# 3_INTERFACE_PWR_LS_HS.net
KiCad netlist of a schematic drawn in Altium Designer
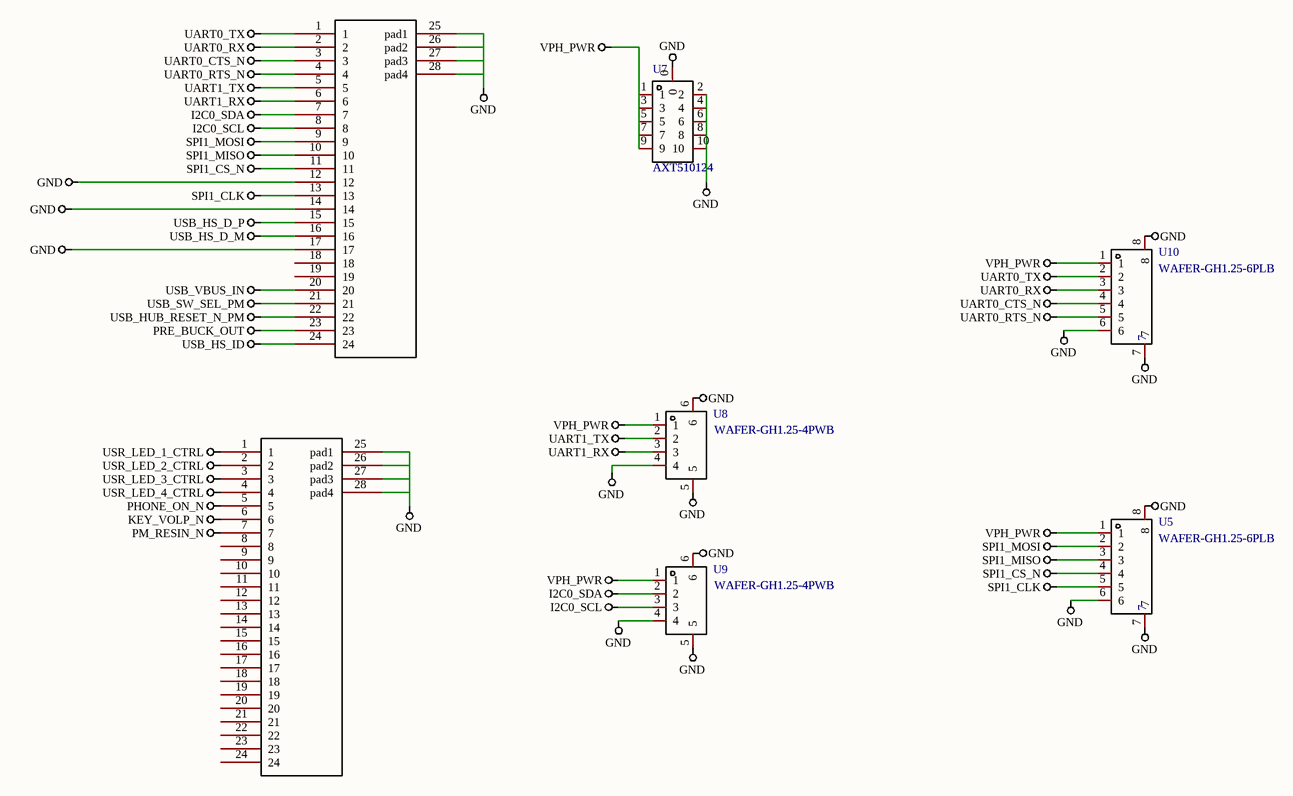
[diagram p0: 3_INTERFACE_PWR_LS_HS.schdoc]

(export (version "E")
  (design (tool "Eeschema 10.0.6"))
  (components
    (comp (ref "CN1")
      (value "CON24_0")
      (fields (field (name "LIBRARY NAME") "MSM8916_DRAM_PMIC_REF_Library"))
      (libsource (lib "altium-import") (part "root_0_CON24_0_"))
    )
    (comp (ref "CN2")
      (value "CON24_0")
      (fields (field (name "LIBRARY NAME") "MSM8916_DRAM_PMIC_REF_Library"))
      (libsource (lib "altium-import") (part "root_0_CON24_0_"))
    )
    (comp (ref "U5")
      (value "WAFER-GH1.25-6PLB")
      (description "参考系列:GH;间距:1.25mm;插针结构:1x6P;排数:1;每排PIN数:6;公母:公型插针;安装方式:立贴;额定电流:1A;工作温度范围:-25℃~+85℃;")
      (fields
        (field (name "NAME") "WAFER-GH1.25-6PLB")
        (field (name "MANUFACTURER") "XUNPU(讯普)")
        (field (name "NAME_1") "7")
      )
      (libsource (lib "altium-import") (part "root_0_WAFER-GH1.25-6PLB_"))
    )
    (comp (ref "U7")
      (value "AXT510124")
      (description "PIN总数:10;间距:0.4mm;行数:2;公母:母;安装方式:立贴;")
      (fields (field (name "NAME") "AXT510124") (field (name "MANUFACTURER") "PANASONIC(松下)"))
      (libsource (lib "altium-import") (part "root_0_AXT510124_"))
    )
    (comp (ref "U8")
      (value "WAFER-GH1.25-4PWB")
      (description "参考系列:GH;间距:1.25mm;插针结构:1x4P;排数:1;每排PIN数:4;公母:公型插针;安装方式:卧贴;额定电流:1A;工作温度范围:-25℃~+85℃;")
      (fields (field (name "NAME") "WAFER-GH1.25-4PWB") (field (name "MANUFACTURER") "XUNPU(讯普)"))
      (libsource (lib "altium-import") (part "root_0_WAFER-GH1.25-4PWB_"))
    )
    (comp (ref "U9")
      (value "WAFER-GH1.25-4PWB")
      (description "参考系列:GH;间距:1.25mm;插针结构:1x4P;排数:1;每排PIN数:4;公母:公型插针;安装方式:卧贴;额定电流:1A;工作温度范围:-25℃~+85℃;")
      (fields (field (name "NAME") "WAFER-GH1.25-4PWB") (field (name "MANUFACTURER") "XUNPU(讯普)"))
      (libsource (lib "altium-import") (part "root_0_WAFER-GH1.25-4PWB_"))
    )
    (comp (ref "U10")
      (value "WAFER-GH1.25-6PLB")
      (description "参考系列:GH;间距:1.25mm;插针结构:1x6P;排数:1;每排PIN数:6;公母:公型插针;安装方式:立贴;额定电流:1A;工作温度范围:-25℃~+85℃;")
      (fields
        (field (name "NAME") "WAFER-GH1.25-6PLB")
        (field (name "MANUFACTURER") "XUNPU(讯普)")
        (field (name "NAME_1") "7")
      )
      (libsource (lib "altium-import") (part "root_0_WAFER-GH1.25-6PLB_"))
    )
  )
  (nets
    (net (code "1") (name "GND") (class "Default")
      (node (ref "CN1") (pin "12") (pinfunction "12_12") (pintype "passive"))
      (node (ref "CN1") (pin "14") (pinfunction "14_14") (pintype "passive"))
      (node (ref "CN1") (pin "17") (pinfunction "17_17") (pintype "passive"))
      (node (ref "CN1") (pin "25") (pinfunction "pad1_25") (pintype "passive"))
      (node (ref "CN1") (pin "26") (pinfunction "pad2_26") (pintype "passive"))
      (node (ref "CN1") (pin "27") (pinfunction "pad3_27") (pintype "passive"))
      (node (ref "CN1") (pin "28") (pinfunction "pad4_28") (pintype "passive"))
      (node (ref "CN2") (pin "25") (pinfunction "pad1_25") (pintype "passive"))
      (node (ref "CN2") (pin "26") (pinfunction "pad2_26") (pintype "passive"))
      (node (ref "CN2") (pin "27") (pinfunction "pad3_27") (pintype "passive"))
      (node (ref "CN2") (pin "28") (pinfunction "pad4_28") (pintype "passive"))
      (node (ref "U10") (pin "6") (pinfunction "6_6") (pintype "passive"))
      (node (ref "U10") (pin "7") (pinfunction "7_7") (pintype "passive"))
      (node (ref "U10") (pin "8") (pinfunction "8_8") (pintype "passive"))
      (node (ref "U5") (pin "6") (pinfunction "6_6") (pintype "passive"))
      (node (ref "U5") (pin "7") (pinfunction "7_7") (pintype "passive"))
      (node (ref "U5") (pin "8") (pinfunction "8_8") (pintype "passive"))
      (node (ref "U7") (pin "0") (pinfunction "0_0") (pintype "passive"))
      (node (ref "U7") (pin "10") (pinfunction "10_10") (pintype "passive"))
      (node (ref "U7") (pin "2") (pinfunction "2_2") (pintype "passive"))
      (node (ref "U7") (pin "4") (pinfunction "4_4") (pintype "passive"))
      (node (ref "U7") (pin "6") (pinfunction "6_6") (pintype "passive"))
      (node (ref "U7") (pin "8") (pinfunction "8_8") (pintype "passive"))
      (node (ref "U8") (pin "4") (pinfunction "4_4") (pintype "passive"))
      (node (ref "U8") (pin "5") (pinfunction "5_5") (pintype "passive"))
      (node (ref "U8") (pin "6") (pinfunction "6_6") (pintype "passive"))
      (node (ref "U9") (pin "4") (pinfunction "4_4") (pintype "passive"))
      (node (ref "U9") (pin "5") (pinfunction "5_5") (pintype "passive"))
      (node (ref "U9") (pin "6") (pinfunction "6_6") (pintype "passive"))
    )
    (net (code "2") (name "I2C0_SCL") (class "Default")
      (node (ref "CN1") (pin "8") (pinfunction "8_8") (pintype "passive"))
      (node (ref "U9") (pin "3") (pinfunction "3_3") (pintype "passive"))
    )
    (net (code "3") (name "I2C0_SDA") (class "Default")
      (node (ref "CN1") (pin "7") (pinfunction "7_7") (pintype "passive"))
      (node (ref "U9") (pin "2") (pinfunction "2_2") (pintype "passive"))
    )
    (net (code "4") (name "KEY_VOLP_N") (class "Default")
      (node (ref "CN2") (pin "6") (pinfunction "6_6") (pintype "passive"))
    )
    (net (code "5") (name "PHONE_ON_N") (class "Default")
      (node (ref "CN2") (pin "5") (pinfunction "5_5") (pintype "passive"))
    )
    (net (code "6") (name "PM_RESIN_N") (class "Default")
      (node (ref "CN2") (pin "7") (pinfunction "7_7") (pintype "passive"))
    )
    (net (code "7") (name "PRE_BUCK_OUT") (class "Default")
      (node (ref "CN1") (pin "23") (pinfunction "23_23") (pintype "passive"))
    )
    (net (code "8") (name "SPI1_CLK") (class "Default")
      (node (ref "CN1") (pin "13") (pinfunction "13_13") (pintype "passive"))
      (node (ref "U5") (pin "5") (pinfunction "5_5") (pintype "passive"))
    )
    (net (code "9") (name "SPI1_CS_N") (class "Default")
      (node (ref "CN1") (pin "11") (pinfunction "11_11") (pintype "passive"))
      (node (ref "U5") (pin "4") (pinfunction "4_4") (pintype "passive"))
    )
    (net (code "10") (name "SPI1_MISO") (class "Default")
      (node (ref "CN1") (pin "10") (pinfunction "10_10") (pintype "passive"))
      (node (ref "U5") (pin "3") (pinfunction "3_3") (pintype "passive"))
    )
    (net (code "11") (name "SPI1_MOSI") (class "Default")
      (node (ref "CN1") (pin "9") (pinfunction "9_9") (pintype "passive"))
      (node (ref "U5") (pin "2") (pinfunction "2_2") (pintype "passive"))
    )
    (net (code "12") (name "UART0_CTS_N") (class "Default")
      (node (ref "CN1") (pin "3") (pinfunction "3_3") (pintype "passive"))
      (node (ref "U10") (pin "4") (pinfunction "4_4") (pintype "passive"))
    )
    (net (code "13") (name "UART0_RTS_N") (class "Default")
      (node (ref "CN1") (pin "4") (pinfunction "4_4") (pintype "passive"))
      (node (ref "U10") (pin "5") (pinfunction "5_5") (pintype "passive"))
    )
    (net (code "14") (name "UART0_RX") (class "Default")
      (node (ref "CN1") (pin "2") (pinfunction "2_2") (pintype "passive"))
      (node (ref "U10") (pin "3") (pinfunction "3_3") (pintype "passive"))
    )
    (net (code "15") (name "UART0_TX") (class "Default")
      (node (ref "CN1") (pin "1") (pinfunction "1_1") (pintype "passive"))
      (node (ref "U10") (pin "2") (pinfunction "2_2") (pintype "passive"))
    )
    (net (code "16") (name "UART1_RX") (class "Default")
      (node (ref "CN1") (pin "6") (pinfunction "6_6") (pintype "passive"))
      (node (ref "U8") (pin "3") (pinfunction "3_3") (pintype "passive"))
    )
    (net (code "17") (name "UART1_TX") (class "Default")
      (node (ref "CN1") (pin "5") (pinfunction "5_5") (pintype "passive"))
      (node (ref "U8") (pin "2") (pinfunction "2_2") (pintype "passive"))
    )
    (net (code "18") (name "USB_HS_D_M") (class "Default")
      (node (ref "CN1") (pin "16") (pinfunction "16_16") (pintype "passive"))
    )
    (net (code "19") (name "USB_HS_D_P") (class "Default")
      (node (ref "CN1") (pin "15") (pinfunction "15_15") (pintype "passive"))
    )
    (net (code "20") (name "USB_HS_ID") (class "Default")
      (node (ref "CN1") (pin "24") (pinfunction "24_24") (pintype "passive"))
    )
    (net (code "21") (name "USB_HUB_RESET_N_PM") (class "Default")
      (node (ref "CN1") (pin "22") (pinfunction "22_22") (pintype "passive"))
    )
    (net (code "22") (name "USB_SW_SEL_PM") (class "Default")
      (node (ref "CN1") (pin "21") (pinfunction "21_21") (pintype "passive"))
    )
    (net (code "23") (name "USB_VBUS_IN") (class "Default")
      (node (ref "CN1") (pin "20") (pinfunction "20_20") (pintype "passive"))
    )
    (net (code "24") (name "USR_LED_1_CTRL") (class "Default")
      (node (ref "CN2") (pin "1") (pinfunction "1_1") (pintype "passive"))
    )
    (net (code "25") (name "USR_LED_2_CTRL") (class "Default")
      (node (ref "CN2") (pin "2") (pinfunction "2_2") (pintype "passive"))
    )
    (net (code "26") (name "USR_LED_3_CTRL") (class "Default")
      (node (ref "CN2") (pin "3") (pinfunction "3_3") (pintype "passive"))
    )
    (net (code "27") (name "USR_LED_4_CTRL") (class "Default")
      (node (ref "CN2") (pin "4") (pinfunction "4_4") (pintype "passive"))
    )
    (net (code "28") (name "VPH_PWR") (class "Default")
      (node (ref "U10") (pin "1") (pinfunction "1_1") (pintype "passive"))
      (node (ref "U5") (pin "1") (pinfunction "1_1") (pintype "passive"))
      (node (ref "U7") (pin "1") (pinfunction "1_1") (pintype "passive"))
      (node (ref "U7") (pin "3") (pinfunction "3_3") (pintype "passive"))
      (node (ref "U7") (pin "5") (pinfunction "5_5") (pintype "passive"))
      (node (ref "U7") (pin "7") (pinfunction "7_7") (pintype "passive"))
      (node (ref "U7") (pin "9") (pinfunction "9_9") (pintype "passive"))
      (node (ref "U8") (pin "1") (pinfunction "1_1") (pintype "passive"))
      (node (ref "U9") (pin "1") (pinfunction "1_1") (pintype "passive"))
    )
    (net (code "29") (name "unconnected-(CN1-Pad18)") (class "Default")
      (node (ref "CN1") (pin "18") (pinfunction "18_18") (pintype "passive"))
    )
    (net (code "30") (name "unconnected-(CN1-Pad19)") (class "Default")
      (node (ref "CN1") (pin "19") (pinfunction "19_19") (pintype "passive"))
    )
    (net (code "31") (name "unconnected-(CN2-Pad8)") (class "Default")
      (node (ref "CN2") (pin "8") (pinfunction "8_8") (pintype "passive"))
    )
    (net (code "32") (name "unconnected-(CN2-Pad9)") (class "Default")
      (node (ref "CN2") (pin "9") (pinfunction "9_9") (pintype "passive"))
    )
    (net (code "33") (name "unconnected-(CN2-Pad10)") (class "Default")
      (node (ref "CN2") (pin "10") (pinfunction "10_10") (pintype "passive"))
    )
    (net (code "34") (name "unconnected-(CN2-Pad11)") (class "Default")
      (node (ref "CN2") (pin "11") (pinfunction "11_11") (pintype "passive"))
    )
    (net (code "35") (name "unconnected-(CN2-Pad12)") (class "Default")
      (node (ref "CN2") (pin "12") (pinfunction "12_12") (pintype "passive"))
    )
    (net (code "36") (name "unconnected-(CN2-Pad13)") (class "Default")
      (node (ref "CN2") (pin "13") (pinfunction "13_13") (pintype "passive"))
    )
    (net (code "37") (name "unconnected-(CN2-Pad14)") (class "Default")
      (node (ref "CN2") (pin "14") (pinfunction "14_14") (pintype "passive"))
    )
    (net (code "38") (name "unconnected-(CN2-Pad15)") (class "Default")
      (node (ref "CN2") (pin "15") (pinfunction "15_15") (pintype "passive"))
    )
    (net (code "39") (name "unconnected-(CN2-Pad16)") (class "Default")
      (node (ref "CN2") (pin "16") (pinfunction "16_16") (pintype "passive"))
    )
    (net (code "40") (name "unconnected-(CN2-Pad17)") (class "Default")
      (node (ref "CN2") (pin "17") (pinfunction "17_17") (pintype "passive"))
    )
    (net (code "41") (name "unconnected-(CN2-Pad18)") (class "Default")
      (node (ref "CN2") (pin "18") (pinfunction "18_18") (pintype "passive"))
    )
    (net (code "42") (name "unconnected-(CN2-Pad19)") (class "Default")
      (node (ref "CN2") (pin "19") (pinfunction "19_19") (pintype "passive"))
    )
    (net (code "43") (name "unconnected-(CN2-Pad20)") (class "Default")
      (node (ref "CN2") (pin "20") (pinfunction "20_20") (pintype "passive"))
    )
    (net (code "44") (name "unconnected-(CN2-Pad21)") (class "Default")
      (node (ref "CN2") (pin "21") (pinfunction "21_21") (pintype "passive"))
    )
    (net (code "45") (name "unconnected-(CN2-Pad22)") (class "Default")
      (node (ref "CN2") (pin "22") (pinfunction "22_22") (pintype "passive"))
    )
    (net (code "46") (name "unconnected-(CN2-Pad23)") (class "Default")
      (node (ref "CN2") (pin "23") (pinfunction "23_23") (pintype "passive"))
    )
    (net (code "47") (name "unconnected-(CN2-Pad24)") (class "Default")
      (node (ref "CN2") (pin "24") (pinfunction "24_24") (pintype "passive"))
    )
  )
)
